# 2m_70cm_diplexer.net
KiCad netlist of a schematic drawn in EAGLE
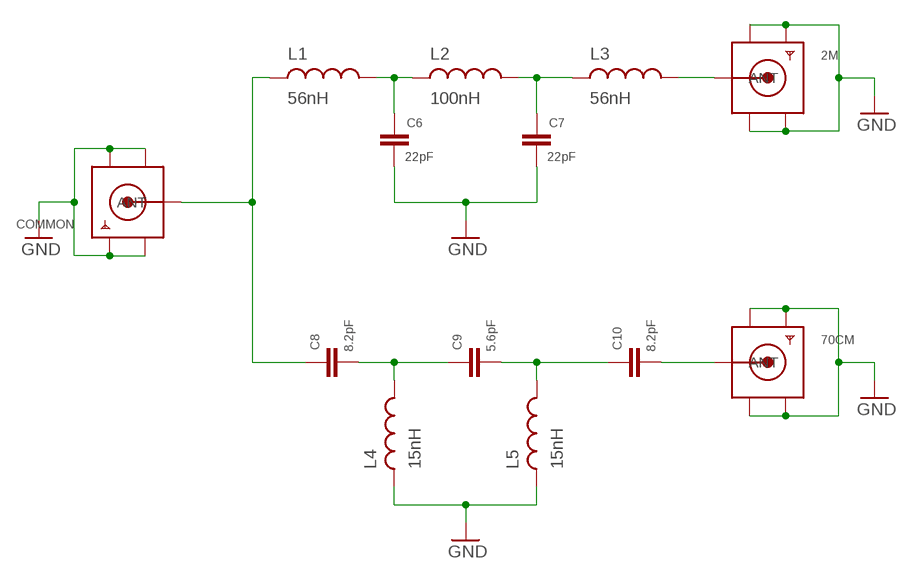
[diagram p0: schematic, sheet 1]

(export (version "E")
  (design (tool "Eeschema 10.0.6"))
  (components
    (comp (ref "2M")
      (value "SMACONNECTOR_EDGE")
      (footprint "eagle-import:SMA_EDGELAUNCH")
      (libsource (lib "eagle-import") (part "SMACONNECTOR_EDGE"))
    )
    (comp (ref "70CM")
      (value "SMACONNECTOR_EDGE")
      (footprint "eagle-import:SMA_EDGELAUNCH")
      (libsource (lib "eagle-import") (part "SMACONNECTOR_EDGE"))
    )
    (comp (ref "C6")
      (value "22pF")
      (footprint "eagle-import:0805")
      (libsource (lib "eagle-import") (part "0805CAP"))
    )
    (comp (ref "C7")
      (value "22pF")
      (footprint "eagle-import:0805")
      (libsource (lib "eagle-import") (part "0805CAP"))
    )
    (comp (ref "C8")
      (value "8.2pF")
      (footprint "eagle-import:0805")
      (libsource (lib "eagle-import") (part "0805CAP"))
    )
    (comp (ref "C9")
      (value "5.6pF")
      (footprint "eagle-import:0805")
      (libsource (lib "eagle-import") (part "0805CAP"))
    )
    (comp (ref "C10")
      (value "8.2pF")
      (footprint "eagle-import:0805")
      (libsource (lib "eagle-import") (part "0805CAP"))
    )
    (comp (ref "COMMON")
      (value "SMACONNECTOR_EDGE")
      (footprint "eagle-import:SMA_EDGELAUNCH")
      (libsource (lib "eagle-import") (part "SMACONNECTOR_EDGE"))
    )
    (comp (ref "L1")
      (value "56nH")
      (footprint "eagle-import:1008INDUCTOR")
      (libsource (lib "eagle-import") (part "1008INDUCTOR"))
    )
    (comp (ref "L2")
      (value "100nH")
      (footprint "eagle-import:1008INDUCTOR")
      (libsource (lib "eagle-import") (part "1008INDUCTOR"))
    )
    (comp (ref "L3")
      (value "56nH")
      (footprint "eagle-import:1008INDUCTOR")
      (libsource (lib "eagle-import") (part "1008INDUCTOR"))
    )
    (comp (ref "L4")
      (value "15nH")
      (footprint "eagle-import:1008INDUCTOR")
      (libsource (lib "eagle-import") (part "1008INDUCTOR"))
    )
    (comp (ref "L5")
      (value "15nH")
      (footprint "eagle-import:1008INDUCTOR")
      (libsource (lib "eagle-import") (part "1008INDUCTOR"))
    )
  )
  (nets
    (net (code "1") (name "GND") (class "Default")
      (node (ref "2M") (pin "GND@1") (pinfunction "GND4_GND@1") (pintype "power_in"))
      (node (ref "2M") (pin "GND@2") (pinfunction "GND3_GND@2") (pintype "power_in"))
      (node (ref "2M") (pin "GND@3") (pinfunction "GND2_GND@3") (pintype "power_in"))
      (node (ref "2M") (pin "GND@4") (pinfunction "GND1_GND@4") (pintype "power_in"))
      (node (ref "70CM") (pin "GND@1") (pinfunction "GND4_GND@1") (pintype "power_in"))
      (node (ref "70CM") (pin "GND@2") (pinfunction "GND3_GND@2") (pintype "power_in"))
      (node (ref "70CM") (pin "GND@3") (pinfunction "GND2_GND@3") (pintype "power_in"))
      (node (ref "70CM") (pin "GND@4") (pinfunction "GND1_GND@4") (pintype "power_in"))
      (node (ref "C6") (pin "P$1") (pinfunction "P$1_P$1") (pintype "bidirectional"))
      (node (ref "C7") (pin "P$1") (pinfunction "P$1_P$1") (pintype "bidirectional"))
      (node (ref "COMMON") (pin "GND@1") (pinfunction "GND4_GND@1") (pintype "power_in"))
      (node (ref "COMMON") (pin "GND@2") (pinfunction "GND3_GND@2") (pintype "power_in"))
      (node (ref "COMMON") (pin "GND@3") (pinfunction "GND2_GND@3") (pintype "power_in"))
      (node (ref "COMMON") (pin "GND@4") (pinfunction "GND1_GND@4") (pintype "power_in"))
      (node (ref "L4") (pin "P$1") (pinfunction "P$1_P$1") (pintype "bidirectional"))
      (node (ref "L5") (pin "P$1") (pinfunction "P$1_P$1") (pintype "bidirectional"))
    )
    (net (code "2") (name "Net-(2M-ANT)") (class "Default")
      (node (ref "2M") (pin "P") (pinfunction "ANT_P") (pintype "bidirectional"))
      (node (ref "L3") (pin "P$2") (pinfunction "P$2_P$2") (pintype "bidirectional"))
    )
    (net (code "3") (name "Net-(70CM-ANT)") (class "Default")
      (node (ref "70CM") (pin "P") (pinfunction "ANT_P") (pintype "bidirectional"))
      (node (ref "C10") (pin "P$1") (pinfunction "P$1_P$1") (pintype "bidirectional"))
    )
    (net (code "4") (name "Net-(C6-PadP$2)") (class "Default")
      (node (ref "C6") (pin "P$2") (pinfunction "P$2_P$2") (pintype "bidirectional"))
      (node (ref "L1") (pin "P$2") (pinfunction "P$2_P$2") (pintype "bidirectional"))
      (node (ref "L2") (pin "P$1") (pinfunction "P$1_P$1") (pintype "bidirectional"))
    )
    (net (code "5") (name "Net-(C7-PadP$2)") (class "Default")
      (node (ref "C7") (pin "P$2") (pinfunction "P$2_P$2") (pintype "bidirectional"))
      (node (ref "L2") (pin "P$2") (pinfunction "P$2_P$2") (pintype "bidirectional"))
      (node (ref "L3") (pin "P$1") (pinfunction "P$1_P$1") (pintype "bidirectional"))
    )
    (net (code "6") (name "Net-(C8-PadP$1)") (class "Default")
      (node (ref "C8") (pin "P$1") (pinfunction "P$1_P$1") (pintype "bidirectional"))
      (node (ref "C9") (pin "P$2") (pinfunction "P$2_P$2") (pintype "bidirectional"))
      (node (ref "L4") (pin "P$2") (pinfunction "P$2_P$2") (pintype "bidirectional"))
    )
    (net (code "7") (name "Net-(C10-PadP$2)") (class "Default")
      (node (ref "C10") (pin "P$2") (pinfunction "P$2_P$2") (pintype "bidirectional"))
      (node (ref "C9") (pin "P$1") (pinfunction "P$1_P$1") (pintype "bidirectional"))
      (node (ref "L5") (pin "P$2") (pinfunction "P$2_P$2") (pintype "bidirectional"))
    )
    (net (code "8") (name "Net-(COMMON-ANT)") (class "Default")
      (node (ref "C8") (pin "P$2") (pinfunction "P$2_P$2") (pintype "bidirectional"))
      (node (ref "COMMON") (pin "P") (pinfunction "ANT_P") (pintype "bidirectional"))
      (node (ref "L1") (pin "P$1") (pinfunction "P$1_P$1") (pintype "bidirectional"))
    )
  )
)
